# aaLogger.net
KiCad netlist of a schematic drawn in EAGLE
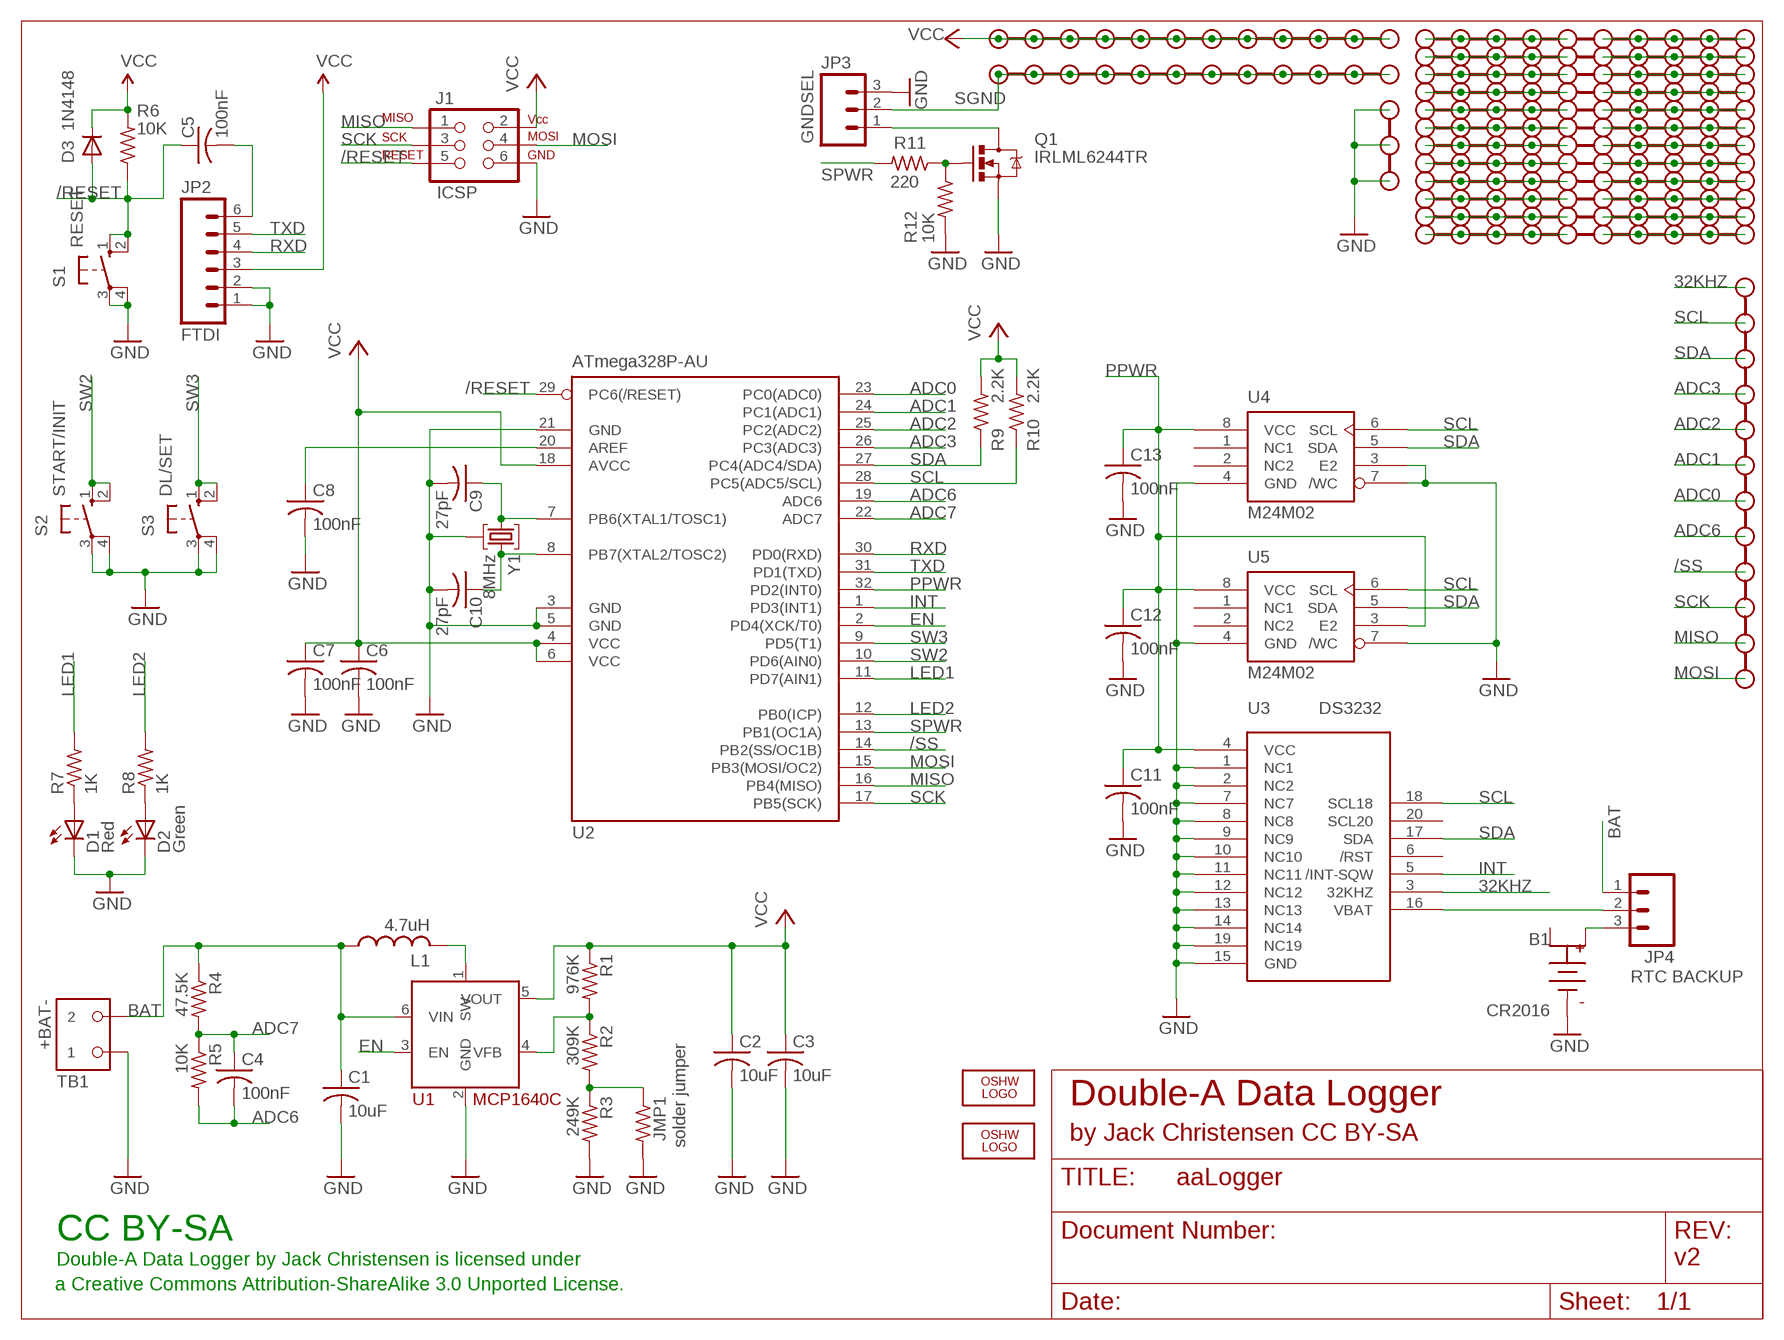
[diagram p0: schematic, sheet 1]

(export (version "E")
  (design (tool "Eeschema 10.0.6"))
  (components
    (comp (ref "B1")
      (value "CR2016")
      (footprint "eagle-import:BAT-HLD-002-SMT")
      (libsource (lib "eagle-import") (part "COIN-CELL-2016-SMT"))
    )
    (comp (ref "C1")
      (value "10uF")
      (footprint "eagle-import:M0805")
      (libsource (lib "eagle-import") (part "C-USM0805"))
    )
    (comp (ref "C2")
      (value "10uF")
      (footprint "eagle-import:M0805")
      (libsource (lib "eagle-import") (part "C-USM0805"))
    )
    (comp (ref "C3")
      (value "10uF")
      (footprint "eagle-import:M0805")
      (libsource (lib "eagle-import") (part "C-USM0805"))
    )
    (comp (ref "C4")
      (value "100nF")
      (footprint "eagle-import:M0805")
      (libsource (lib "eagle-import") (part "C-USM0805"))
    )
    (comp (ref "C5")
      (value "100nF")
      (footprint "eagle-import:M0805")
      (libsource (lib "eagle-import") (part "C-USM0805"))
    )
    (comp (ref "C6")
      (value "100nF")
      (footprint "eagle-import:M0805")
      (libsource (lib "eagle-import") (part "C-USM0805"))
    )
    (comp (ref "C7")
      (value "100nF")
      (footprint "eagle-import:M0805")
      (libsource (lib "eagle-import") (part "C-USM0805"))
    )
    (comp (ref "C8")
      (value "100nF")
      (footprint "eagle-import:M0805")
      (libsource (lib "eagle-import") (part "C-USM0805"))
    )
    (comp (ref "C9")
      (value "27pF")
      (footprint "eagle-import:M0805")
      (libsource (lib "eagle-import") (part "C-USM0805"))
    )
    (comp (ref "C10")
      (value "27pF")
      (footprint "eagle-import:M0805")
      (libsource (lib "eagle-import") (part "C-USM0805"))
    )
    (comp (ref "C11")
      (value "100nF")
      (footprint "eagle-import:M0805")
      (libsource (lib "eagle-import") (part "C-USM0805"))
    )
    (comp (ref "C12")
      (value "100nF")
      (footprint "eagle-import:M0805")
      (libsource (lib "eagle-import") (part "C-USM0805"))
    )
    (comp (ref "C13")
      (value "100nF")
      (footprint "eagle-import:M0805")
      (libsource (lib "eagle-import") (part "C-USM0805"))
    )
    (comp (ref "D1")
      (value "Red")
      (footprint "eagle-import:CHIPLED_1206")
      (libsource (lib "eagle-import") (part "LEDCHIPLED_1206"))
    )
    (comp (ref "D2")
      (value "Green")
      (footprint "eagle-import:CHIPLED_1206")
      (libsource (lib "eagle-import") (part "LEDCHIPLED_1206"))
    )
    (comp (ref "D3")
      (value "1N4148")
      (footprint "eagle-import:SOD-323F")
      (libsource (lib "eagle-import") (part "DIODESOD-323F"))
    )
    (comp (ref "J1")
      (value "ICSP")
      (footprint "eagle-import:2X3_LOCK")
      (libsource (lib "eagle-import") (part "AVR_SPI_PRG_62X3_LOCK"))
    )
    (comp (ref "JMP1")
      (value "solder jumper")
      (footprint "eagle-import:M0805")
      (libsource (lib "eagle-import") (part "R-US_M0805"))
    )
    (comp (ref "JP1")
      (value "PROTO-12NR")
      (footprint "eagle-import:PROTO-12-NR")
      (libsource (lib "eagle-import") (part "PROTO-12NR"))
    )
    (comp (ref "JP2")
      (value "FTDI")
      (footprint "eagle-import:1X06_LOCK")
      (libsource (lib "eagle-import") (part "M06LOCK"))
    )
    (comp (ref "JP3")
      (value "GNDSEL")
      (footprint "eagle-import:1X03_LOCK")
      (libsource (lib "eagle-import") (part "M03LOCK"))
    )
    (comp (ref "JP4")
      (value "RTC BACKUP")
      (footprint "eagle-import:1X03_LOCK")
      (libsource (lib "eagle-import") (part "M03LOCK"))
    )
    (comp (ref "L1")
      (value "4.7uH")
      (footprint "eagle-import:NRS5020")
      (libsource (lib "eagle-import") (part "INDUCTORNRS5020"))
    )
    (comp (ref "LOGO1")
      (value "OSHW_LOGO_8MILX0150-NT")
      (footprint "eagle-import:OSHW_8X150_NOTEXT")
      (libsource (lib "eagle-import") (part "OSHW_LOGO_8MILX0150-NT"))
    )
    (comp (ref "LOGO2")
      (value "OSHW_LOGO_8MILX0150-NT")
      (footprint "eagle-import:OSHW_8X150_NOTEXT")
      (libsource (lib "eagle-import") (part "OSHW_LOGO_8MILX0150-NT"))
    )
    (comp (ref "PR1")
      (value "PROTO-10")
      (footprint "eagle-import:PROTO-10")
      (libsource (lib "eagle-import") (part "PROTO-10"))
    )
    (comp (ref "PR2")
      (value "PROTO-10")
      (footprint "eagle-import:PROTO-10")
      (libsource (lib "eagle-import") (part "PROTO-10"))
    )
    (comp (ref "PR3")
      (value "PROTO-10")
      (footprint "eagle-import:PROTO-10")
      (libsource (lib "eagle-import") (part "PROTO-10"))
    )
    (comp (ref "PR4")
      (value "PROTO-10")
      (footprint "eagle-import:PROTO-10")
      (libsource (lib "eagle-import") (part "PROTO-10"))
    )
    (comp (ref "PR5")
      (value "PROTO-10")
      (footprint "eagle-import:PROTO-10")
      (libsource (lib "eagle-import") (part "PROTO-10"))
    )
    (comp (ref "PR6")
      (value "PROTO-10")
      (footprint "eagle-import:PROTO-10")
      (libsource (lib "eagle-import") (part "PROTO-10"))
    )
    (comp (ref "PR7")
      (value "PROTO-10")
      (footprint "eagle-import:PROTO-10")
      (libsource (lib "eagle-import") (part "PROTO-10"))
    )
    (comp (ref "PR8")
      (value "PROTO-10")
      (footprint "eagle-import:PROTO-10")
      (libsource (lib "eagle-import") (part "PROTO-10"))
    )
    (comp (ref "PR9")
      (value "PROTO-10")
      (footprint "eagle-import:PROTO-10")
      (libsource (lib "eagle-import") (part "PROTO-10"))
    )
    (comp (ref "PR10")
      (value "PROTO-10")
      (footprint "eagle-import:PROTO-10")
      (libsource (lib "eagle-import") (part "PROTO-10"))
    )
    (comp (ref "PR11")
      (value "PROTO-10")
      (footprint "eagle-import:PROTO-10")
      (libsource (lib "eagle-import") (part "PROTO-10"))
    )
    (comp (ref "PR12")
      (value "PROTO-10")
      (footprint "eagle-import:PROTO-10")
      (libsource (lib "eagle-import") (part "PROTO-10"))
    )
    (comp (ref "PR13")
      (value "PROTO-3")
      (footprint "eagle-import:PROTO-3")
      (libsource (lib "eagle-import") (part "PROTO-3"))
    )
    (comp (ref "Q1")
      (value "IRLML6244TR")
      (footprint "eagle-import:SOT23")
      (libsource (lib "eagle-import") (part "MOSFET-NCHANNELSOT23"))
    )
    (comp (ref "R1")
      (value "976K")
      (footprint "eagle-import:M0805")
      (libsource (lib "eagle-import") (part "R-US_M0805"))
    )
    (comp (ref "R2")
      (value "309K")
      (footprint "eagle-import:M0805")
      (libsource (lib "eagle-import") (part "R-US_M0805"))
    )
    (comp (ref "R3")
      (value "249K")
      (footprint "eagle-import:M0805")
      (libsource (lib "eagle-import") (part "R-US_M0805"))
    )
    (comp (ref "R4")
      (value "47.5K")
      (footprint "eagle-import:M0805")
      (libsource (lib "eagle-import") (part "R-US_M0805"))
    )
    (comp (ref "R5")
      (value "10K")
      (footprint "eagle-import:M0805")
      (libsource (lib "eagle-import") (part "R-US_M0805"))
    )
    (comp (ref "R6")
      (value "10K")
      (footprint "eagle-import:M0805")
      (libsource (lib "eagle-import") (part "R-US_M0805"))
    )
    (comp (ref "R7")
      (value "1K")
      (footprint "eagle-import:M0805")
      (libsource (lib "eagle-import") (part "R-US_M0805"))
    )
    (comp (ref "R8")
      (value "1K")
      (footprint "eagle-import:M0805")
      (libsource (lib "eagle-import") (part "R-US_M0805"))
    )
    (comp (ref "R9")
      (value "2.2K")
      (footprint "eagle-import:M0805")
      (libsource (lib "eagle-import") (part "R-US_M0805"))
    )
    (comp (ref "R10")
      (value "2.2K")
      (footprint "eagle-import:M0805")
      (libsource (lib "eagle-import") (part "R-US_M0805"))
    )
    (comp (ref "R11")
      (value "220")
      (footprint "eagle-import:M0805")
      (libsource (lib "eagle-import") (part "R-US_M0805"))
    )
    (comp (ref "R12")
      (value "10K")
      (footprint "eagle-import:M0805")
      (libsource (lib "eagle-import") (part "R-US_M0805"))
    )
    (comp (ref "S1")
      (value "RESET")
      (footprint "eagle-import:B3F-10XXOCT")
      (libsource (lib "eagle-import") (part "10-XXOCT"))
    )
    (comp (ref "S2")
      (value "START/INIT")
      (footprint "eagle-import:B3F-10XXOCT")
      (libsource (lib "eagle-import") (part "10-XXOCT"))
    )
    (comp (ref "S3")
      (value "DL/SET")
      (footprint "eagle-import:B3F-10XXOCT")
      (libsource (lib "eagle-import") (part "10-XXOCT"))
    )
    (comp (ref "TB1")
      (value "+BAT-")
      (footprint "eagle-import:OST-TB-2-3.5MM")
      (libsource (lib "eagle-import") (part "OST-TB-23.5MM"))
    )
    (comp (ref "U$1")
      (value "PROTO-12PROTO")
      (footprint "eagle-import:PROTO-12")
      (libsource (lib "eagle-import") (part "PROTO-12PROTO"))
    )
    (comp (ref "U$2")
      (value "PROTO-12PROTO")
      (footprint "eagle-import:PROTO-12")
      (libsource (lib "eagle-import") (part "PROTO-12PROTO"))
    )
    (comp (ref "U1")
      (value "MCP1640C")
      (footprint "eagle-import:SOT23-6")
      (libsource (lib "eagle-import") (part "MCP1640"))
    )
    (comp (ref "U2")
      (value "ATmega328P-AU")
      (footprint "eagle-import:TQFP32-08")
      (fields (field (name "MPN") "ATMEGA8-16AU"))
      (libsource (lib "eagle-import") (part "MEGA8-AI"))
    )
    (comp (ref "U3")
      (value "DS3232")
      (footprint "eagle-import:SO20W")
      (libsource (lib "eagle-import") (part "DS3232"))
    )
    (comp (ref "U4")
      (value "M24M02")
      (footprint "eagle-import:SO08")
      (libsource (lib "eagle-import") (part "M24M02"))
    )
    (comp (ref "U5")
      (value "M24M02")
      (footprint "eagle-import:SO08")
      (libsource (lib "eagle-import") (part "M24M02"))
    )
    (comp (ref "Y1")
      (value "8MHz")
      (footprint "eagle-import:RESONATOR")
      (libsource (lib "eagle-import") (part "RESONATOR"))
    )
  )
  (nets
    (net (code "1") (name "/32KHZ") (class "Default")
      (node (ref "JP1") (pin "1") (pinfunction "1_1") (pintype "bidirectional"))
      (node (ref "U3") (pin "3") (pinfunction "32KHZ_3") (pintype "bidirectional"))
    )
    (net (code "2") (name "/ADC0") (class "Default")
      (node (ref "JP1") (pin "7") (pinfunction "7_7") (pintype "bidirectional"))
      (node (ref "U2") (pin "23") (pinfunction "PC0(ADC0)_23") (pintype "bidirectional"))
    )
    (net (code "3") (name "/ADC1") (class "Default")
      (node (ref "JP1") (pin "6") (pinfunction "6_6") (pintype "bidirectional"))
      (node (ref "U2") (pin "24") (pinfunction "PC1(ADC1)_24") (pintype "bidirectional"))
    )
    (net (code "4") (name "/ADC2") (class "Default")
      (node (ref "JP1") (pin "5") (pinfunction "5_5") (pintype "bidirectional"))
      (node (ref "U2") (pin "25") (pinfunction "PC2(ADC2)_25") (pintype "bidirectional"))
    )
    (net (code "5") (name "/ADC3") (class "Default")
      (node (ref "JP1") (pin "4") (pinfunction "4_4") (pintype "bidirectional"))
      (node (ref "U2") (pin "26") (pinfunction "PC3(ADC3)_26") (pintype "bidirectional"))
    )
    (net (code "6") (name "/ADC6") (class "Default")
      (node (ref "C4") (pin "2") (pinfunction "2_2") (pintype "passive"))
      (node (ref "JP1") (pin "8") (pinfunction "8_8") (pintype "bidirectional"))
      (node (ref "R5") (pin "2") (pinfunction "2_2") (pintype "passive"))
      (node (ref "U2") (pin "19") (pinfunction "ADC6_19") (pintype "bidirectional"))
    )
    (net (code "7") (name "/ADC7") (class "Default")
      (node (ref "C4") (pin "1") (pinfunction "1_1") (pintype "passive"))
      (node (ref "R4") (pin "2") (pinfunction "2_2") (pintype "passive"))
      (node (ref "R5") (pin "1") (pinfunction "1_1") (pintype "passive"))
      (node (ref "U2") (pin "22") (pinfunction "ADC7_22") (pintype "bidirectional"))
    )
    (net (code "8") (name "/BAT") (class "Default")
      (node (ref "C1") (pin "1") (pinfunction "1_1") (pintype "passive"))
      (node (ref "JP4") (pin "1") (pinfunction "1_1") (pintype "passive"))
      (node (ref "L1") (pin "P$1") (pinfunction "1_P$1") (pintype "passive"))
      (node (ref "R4") (pin "1") (pinfunction "1_1") (pintype "passive"))
      (node (ref "TB1") (pin "P$2") (pinfunction "2_P$2") (pintype "passive"))
      (node (ref "U1") (pin "6") (pinfunction "VIN_6") (pintype "passive"))
    )
    (net (code "9") (name "/EN") (class "Default")
      (node (ref "U1") (pin "3") (pinfunction "EN_3") (pintype "passive"))
      (node (ref "U2") (pin "2") (pinfunction "PD4(XCK/T0)_2") (pintype "bidirectional"))
    )
    (net (code "10") (name "/INT") (class "Default")
      (node (ref "U2") (pin "1") (pinfunction "PD3(INT1)_1") (pintype "bidirectional"))
      (node (ref "U3") (pin "5") (pinfunction "/INT-SQW_5") (pintype "bidirectional"))
    )
    (net (code "11") (name "/LED1") (class "Default")
      (node (ref "R7") (pin "2") (pinfunction "2_2") (pintype "passive"))
      (node (ref "U2") (pin "11") (pinfunction "PD7(AIN1)_11") (pintype "bidirectional"))
    )
    (net (code "12") (name "/LED2") (class "Default")
      (node (ref "R8") (pin "2") (pinfunction "2_2") (pintype "passive"))
      (node (ref "U2") (pin "12") (pinfunction "PB0(ICP)_12") (pintype "bidirectional"))
    )
    (net (code "13") (name "/MISO") (class "Default")
      (node (ref "J1") (pin "1") (pinfunction "1_1") (pintype "passive"))
      (node (ref "JP1") (pin "11") (pinfunction "11_11") (pintype "bidirectional"))
      (node (ref "U2") (pin "16") (pinfunction "PB4(MISO)_16") (pintype "bidirectional"))
    )
    (net (code "14") (name "/MOSI") (class "Default")
      (node (ref "J1") (pin "4") (pinfunction "4_4") (pintype "passive"))
      (node (ref "JP1") (pin "12") (pinfunction "12_12") (pintype "bidirectional"))
      (node (ref "U2") (pin "15") (pinfunction "PB3(MOSI/OC2)_15") (pintype "bidirectional"))
    )
    (net (code "15") (name "/PPWR") (class "Default")
      (node (ref "C11") (pin "1") (pinfunction "1_1") (pintype "passive"))
      (node (ref "C12") (pin "1") (pinfunction "1_1") (pintype "passive"))
      (node (ref "C13") (pin "1") (pinfunction "1_1") (pintype "passive"))
      (node (ref "U2") (pin "32") (pinfunction "PD2(INT0)_32") (pintype "bidirectional"))
      (node (ref "U3") (pin "4") (pinfunction "VCC_4") (pintype "bidirectional"))
      (node (ref "U4") (pin "8") (pinfunction "VCC_8") (pintype "bidirectional"))
      (node (ref "U5") (pin "3") (pinfunction "E2_3") (pintype "bidirectional"))
      (node (ref "U5") (pin "8") (pinfunction "VCC_8") (pintype "bidirectional"))
    )
    (net (code "16") (name "/RXD") (class "Default")
      (node (ref "JP2") (pin "4") (pinfunction "4_4") (pintype "passive"))
      (node (ref "U2") (pin "30") (pinfunction "PD0(RXD)_30") (pintype "bidirectional"))
    )
    (net (code "17") (name "/SCK") (class "Default")
      (node (ref "J1") (pin "3") (pinfunction "3_3") (pintype "passive"))
      (node (ref "JP1") (pin "10") (pinfunction "10_10") (pintype "bidirectional"))
      (node (ref "U2") (pin "17") (pinfunction "PB5(SCK)_17") (pintype "bidirectional"))
    )
    (net (code "18") (name "/SCL") (class "Default")
      (node (ref "JP1") (pin "2") (pinfunction "2_2") (pintype "bidirectional"))
      (node (ref "R10") (pin "1") (pinfunction "1_1") (pintype "passive"))
      (node (ref "U2") (pin "28") (pinfunction "PC5(ADC5/SCL)_28") (pintype "bidirectional"))
      (node (ref "U3") (pin "18") (pinfunction "SCL18_18") (pintype "bidirectional"))
      (node (ref "U4") (pin "6") (pinfunction "SCL_6") (pintype "bidirectional"))
      (node (ref "U5") (pin "6") (pinfunction "SCL_6") (pintype "bidirectional"))
    )
    (net (code "19") (name "/SDA") (class "Default")
      (node (ref "JP1") (pin "3") (pinfunction "3_3") (pintype "bidirectional"))
      (node (ref "R9") (pin "1") (pinfunction "1_1") (pintype "passive"))
      (node (ref "U2") (pin "27") (pinfunction "PC4(ADC4/SDA)_27") (pintype "bidirectional"))
      (node (ref "U3") (pin "17") (pinfunction "SDA_17") (pintype "bidirectional"))
      (node (ref "U4") (pin "5") (pinfunction "SDA_5") (pintype "bidirectional"))
      (node (ref "U5") (pin "5") (pinfunction "SDA_5") (pintype "bidirectional"))
    )
    (net (code "20") (name "/SGND") (class "Default")
      (node (ref "JP3") (pin "2") (pinfunction "2_2") (pintype "passive"))
      (node (ref "U$2") (pin "1") (pinfunction "1_1") (pintype "bidirectional"))
      (node (ref "U$2") (pin "10") (pinfunction "10_10") (pintype "bidirectional"))
      (node (ref "U$2") (pin "11") (pinfunction "11_11") (pintype "bidirectional"))
      (node (ref "U$2") (pin "12") (pinfunction "12_12") (pintype "bidirectional"))
      (node (ref "U$2") (pin "2") (pinfunction "2_2") (pintype "bidirectional"))
      (node (ref "U$2") (pin "3") (pinfunction "3_3") (pintype "bidirectional"))
      (node (ref "U$2") (pin "4") (pinfunction "4_4") (pintype "bidirectional"))
      (node (ref "U$2") (pin "5") (pinfunction "5_5") (pintype "bidirectional"))
      (node (ref "U$2") (pin "6") (pinfunction "6_6") (pintype "bidirectional"))
      (node (ref "U$2") (pin "7") (pinfunction "7_7") (pintype "bidirectional"))
      (node (ref "U$2") (pin "8") (pinfunction "8_8") (pintype "bidirectional"))
      (node (ref "U$2") (pin "9") (pinfunction "9_9") (pintype "bidirectional"))
    )
    (net (code "21") (name "/SPWR") (class "Default")
      (node (ref "R11") (pin "2") (pinfunction "2_2") (pintype "passive"))
      (node (ref "U2") (pin "13") (pinfunction "PB1(OC1A)_13") (pintype "bidirectional"))
    )
    (net (code "22") (name "/SW2") (class "Default")
      (node (ref "S2") (pin "1") (pinfunction "S_1") (pintype "passive"))
      (node (ref "S2") (pin "2") (pinfunction "S1_2") (pintype "passive"))
      (node (ref "U2") (pin "10") (pinfunction "PD6(AIN0)_10") (pintype "bidirectional"))
    )
    (net (code "23") (name "/SW3") (class "Default")
      (node (ref "S3") (pin "1") (pinfunction "S_1") (pintype "passive"))
      (node (ref "S3") (pin "2") (pinfunction "S1_2") (pintype "passive"))
      (node (ref "U2") (pin "9") (pinfunction "PD5(T1)_9") (pintype "bidirectional"))
    )
    (net (code "24") (name "/TXD") (class "Default")
      (node (ref "JP2") (pin "5") (pinfunction "5_5") (pintype "passive"))
      (node (ref "U2") (pin "31") (pinfunction "PD1(TXD)_31") (pintype "bidirectional"))
    )
    (net (code "25") (name "/{slash}RESET") (class "Default")
      (node (ref "C5") (pin "1") (pinfunction "1_1") (pintype "passive"))
      (node (ref "D3") (pin "A") (pinfunction "A_A") (pintype "passive"))
      (node (ref "J1") (pin "5") (pinfunction "5_5") (pintype "passive"))
      (node (ref "R6") (pin "1") (pinfunction "1_1") (pintype "passive"))
      (node (ref "S1") (pin "1") (pinfunction "S_1") (pintype "passive"))
      (node (ref "S1") (pin "2") (pinfunction "S1_2") (pintype "passive"))
      (node (ref "U2") (pin "29") (pinfunction "PC6(/RESET)_29") (pintype "bidirectional"))
    )
    (net (code "26") (name "/{slash}SS") (class "Default")
      (node (ref "JP1") (pin "9") (pinfunction "9_9") (pintype "bidirectional"))
      (node (ref "U2") (pin "14") (pinfunction "PB2(SS/OC1B)_14") (pintype "bidirectional"))
    )
    (net (code "27") (name "GND") (class "Default")
      (node (ref "B1") (pin "NEG") (pinfunction "B-_NEG") (pintype "passive"))
      (node (ref "C1") (pin "2") (pinfunction "2_2") (pintype "passive"))
      (node (ref "C10") (pin "2") (pinfunction "2_2") (pintype "passive"))
      (node (ref "C11") (pin "2") (pinfunction "2_2") (pintype "passive"))
      (node (ref "C12") (pin "2") (pinfunction "2_2") (pintype "passive"))
      (node (ref "C13") (pin "2") (pinfunction "2_2") (pintype "passive"))
      (node (ref "C2") (pin "2") (pinfunction "2_2") (pintype "passive"))
      (node (ref "C3") (pin "2") (pinfunction "2_2") (pintype "passive"))
      (node (ref "C6") (pin "2") (pinfunction "2_2") (pintype "passive"))
      (node (ref "C7") (pin "2") (pinfunction "2_2") (pintype "passive"))
      (node (ref "C8") (pin "2") (pinfunction "2_2") (pintype "passive"))
      (node (ref "C9") (pin "2") (pinfunction "2_2") (pintype "passive"))
      (node (ref "D1") (pin "C") (pinfunction "C_C") (pintype "passive"))
      (node (ref "D2") (pin "C") (pinfunction "C_C") (pintype "passive"))
      (node (ref "J1") (pin "6") (pinfunction "6_6") (pintype "passive"))
      (node (ref "JMP1") (pin "2") (pinfunction "2_2") (pintype "passive"))
      (node (ref "JP2") (pin "1") (pinfunction "1_1") (pintype "passive"))
      (node (ref "JP2") (pin "2") (pinfunction "2_2") (pintype "passive"))
      (node (ref "JP3") (pin "3") (pinfunction "3_3") (pintype "passive"))
      (node (ref "PR13") (pin "1") (pinfunction "1_1") (pintype "bidirectional"))
      (node (ref "PR13") (pin "2") (pinfunction "2_2") (pintype "bidirectional"))
      (node (ref "PR13") (pin "3") (pinfunction "3_3") (pintype "bidirectional"))
      (node (ref "Q1") (pin "2") (pinfunction "S_2") (pintype "passive"))
      (node (ref "R12") (pin "2") (pinfunction "2_2") (pintype "passive"))
      (node (ref "R3") (pin "2") (pinfunction "2_2") (pintype "passive"))
      (node (ref "S1") (pin "3") (pinfunction "P_3") (pintype "passive"))
      (node (ref "S1") (pin "4") (pinfunction "P1_4") (pintype "passive"))
      (node (ref "S2") (pin "3") (pinfunction "P_3") (pintype "passive"))
      (node (ref "S2") (pin "4") (pinfunction "P1_4") (pintype "passive"))
      (node (ref "S3") (pin "3") (pinfunction "P_3") (pintype "passive"))
      (node (ref "S3") (pin "4") (pinfunction "P1_4") (pintype "passive"))
      (node (ref "TB1") (pin "P$1") (pinfunction "1_P$1") (pintype "passive"))
      (node (ref "U1") (pin "2") (pinfunction "GND_2") (pintype "passive"))
      (node (ref "U2") (pin "21") (pinfunction "GND_21") (pintype "power_in"))
      (node (ref "U2") (pin "3") (pinfunction "GND_3") (pintype "power_in"))
      (node (ref "U2") (pin "5") (pinfunction "GND_5") (pintype "power_in"))
      (node (ref "U3") (pin "1") (pinfunction "NC1_1") (pintype "bidirectional"))
      (node (ref "U3") (pin "10") (pinfunction "NC10_10") (pintype "bidirectional"))
      (node (ref "U3") (pin "11") (pinfunction "NC11_11") (pintype "bidirectional"))
      (node (ref "U3") (pin "12") (pinfunction "NC12_12") (pintype "bidirectional"))
      (node (ref "U3") (pin "13") (pinfunction "NC13_13") (pintype "bidirectional"))
      (node (ref "U3") (pin "14") (pinfunction "NC14_14") (pintype "bidirectional"))
      (node (ref "U3") (pin "15") (pinfunction "GND_15") (pintype "bidirectional"))
      (node (ref "U3") (pin "19") (pinfunction "NC19_19") (pintype "bidirectional"))
      (node (ref "U3") (pin "2") (pinfunction "NC2_2") (pintype "bidirectional"))
      (node (ref "U3") (pin "7") (pinfunction "NC7_7") (pintype "bidirectional"))
      (node (ref "U3") (pin "8") (pinfunction "NC8_8") (pintype "bidirectional"))
      (node (ref "U3") (pin "9") (pinfunction "NC9_9") (pintype "bidirectional"))
      (node (ref "U4") (pin "3") (pinfunction "E2_3") (pintype "bidirectional"))
      (node (ref "U4") (pin "4") (pinfunction "GND_4") (pintype "bidirectional"))
      (node (ref "U4") (pin "7") (pinfunction "/WC_7") (pintype "bidirectional"))
      (node (ref "U5") (pin "4") (pinfunction "GND_4") (pintype "bidirectional"))
      (node (ref "U5") (pin "7") (pinfunction "/WC_7") (pintype "bidirectional"))
      (node (ref "Y1") (pin "2") (pinfunction "2_2") (pintype "passive"))
    )
    (net (code "28") (name "Net-(B1-PadPOS1)") (class "Default")
      (node (ref "B1") (pin "POS1") (pinfunction "POS1_POS1") (pintype "passive"))
      (node (ref "JP4") (pin "3") (pinfunction "3_3") (pintype "passive"))
    )
    (net (code "29") (name "Net-(C5-Pad2)") (class "Default")
      (node (ref "C5") (pin "2") (pinfunction "2_2") (pintype "passive"))
      (node (ref "JP2") (pin "6") (pinfunction "6_6") (pintype "passive"))
    )
    (net (code "30") (name "Net-(D1-PadA)") (class "Default")
      (node (ref "D1") (pin "A") (pinfunction "A_A") (pintype "passive"))
      (node (ref "R7") (pin "1") (pinfunction "1_1") (pintype "passive"))
    )
    (net (code "31") (name "Net-(D2-PadA)") (class "Default")
      (node (ref "D2") (pin "A") (pinfunction "A_A") (pintype "passive"))
      (node (ref "R8") (pin "1") (pinfunction "1_1") (pintype "passive"))
    )
    (net (code "32") (name "Net-(JMP1-Pad1)") (class "Default")
      (node (ref "JMP1") (pin "1") (pinfunction "1_1") (pintype "passive"))
      (node (ref "R2") (pin "2") (pinfunction "2_2") (pintype "passive"))
      (node (ref "R3") (pin "1") (pinfunction "1_1") (pintype "passive"))
    )
    (net (code "33") (name "Net-(L1-2)") (class "Default")
      (node (ref "L1") (pin "P$2") (pinfunction "2_P$2") (pintype "passive"))
      (node (ref "U1") (pin "1") (pinfunction "SW_1") (pintype "passive"))
    )
    (net (code "34") (name "Net-(PR1-Pad1)") (class "Default")
      (node (ref "PR1") (pin "1") (pinfunction "1_1") (pintype "bidirectional"))
      (node (ref "PR1") (pin "2") (pinfunction "2_2") (pintype "bidirectional"))
      (node (ref "PR1") (pin "3") (pinfunction "3_3") (pintype "bidirectional"))
      (node (ref "PR1") (pin "4") (pinfunction "4_4") (pintype "bidirectional"))
      (node (ref "PR1") (pin "5") (pinfunction "5_5") (pintype "bidirectional"))
    )
    (net (code "35") (name "Net-(PR1-Pad10)") (class "Default")
      (node (ref "PR1") (pin "10") (pinfunction "10_10") (pintype "bidirectional"))
      (node (ref "PR1") (pin "6") (pinfunction "6_6") (pintype "bidirectional"))
      (node (ref "PR1") (pin "7") (pinfunction "7_7") (pintype "bidirectional"))
      (node (ref "PR1") (pin "8") (pinfunction "8_8") (pintype "bidirectional"))
      (node (ref "PR1") (pin "9") (pinfunction "9_9") (pintype "bidirectional"))
    )
    (net (code "36") (name "Net-(PR2-Pad1)") (class "Default")
      (node (ref "PR2") (pin "1") (pinfunction "1_1") (pintype "bidirectional"))
      (node (ref "PR2") (pin "2") (pinfunction "2_2") (pintype "bidirectional"))
      (node (ref "PR2") (pin "3") (pinfunction "3_3") (pintype "bidirectional"))
      (node (ref "PR2") (pin "4") (pinfunction "4_4") (pintype "bidirectional"))
      (node (ref "PR2") (pin "5") (pinfunction "5_5") (pintype "bidirectional"))
    )
    (net (code "37") (name "Net-(PR2-Pad10)") (class "Default")
      (node (ref "PR2") (pin "10") (pinfunction "10_10") (pintype "bidirectional"))
      (node (ref "PR2") (pin "6") (pinfunction "6_6") (pintype "bidirectional"))
      (node (ref "PR2") (pin "7") (pinfunction "7_7") (pintype "bidirectional"))
      (node (ref "PR2") (pin "8") (pinfunction "8_8") (pintype "bidirectional"))
      (node (ref "PR2") (pin "9") (pinfunction "9_9") (pintype "bidirectional"))
    )
    (net (code "38") (name "Net-(PR3-Pad1)") (class "Default")
      (node (ref "PR3") (pin "1") (pinfunction "1_1") (pintype "bidirectional"))
      (node (ref "PR3") (pin "2") (pinfunction "2_2") (pintype "bidirectional"))
      (node (ref "PR3") (pin "3") (pinfunction "3_3") (pintype "bidirectional"))
      (node (ref "PR3") (pin "4") (pinfunction "4_4") (pintype "bidirectional"))
      (node (ref "PR3") (pin "5") (pinfunction "5_5") (pintype "bidirectional"))
    )
    (net (code "39") (name "Net-(PR3-Pad10)") (class "Default")
      (node (ref "PR3") (pin "10") (pinfunction "10_10") (pintype "bidirectional"))
      (node (ref "PR3") (pin "6") (pinfunction "6_6") (pintype "bidirectional"))
      (node (ref "PR3") (pin "7") (pinfunction "7_7") (pintype "bidirectional"))
      (node (ref "PR3") (pin "8") (pinfunction "8_8") (pintype "bidirectional"))
      (node (ref "PR3") (pin "9") (pinfunction "9_9") (pintype "bidirectional"))
    )
    (net (code "40") (name "Net-(PR4-Pad1)") (class "Default")
      (node (ref "PR4") (pin "1") (pinfunction "1_1") (pintype "bidirectional"))
      (node (ref "PR4") (pin "2") (pinfunction "2_2") (pintype "bidirectional"))
      (node (ref "PR4") (pin "3") (pinfunction "3_3") (pintype "bidirectional"))
      (node (ref "PR4") (pin "4") (pinfunction "4_4") (pintype "bidirectional"))
      (node (ref "PR4") (pin "5") (pinfunction "5_5") (pintype "bidirectional"))
    )
    (net (code "41") (name "Net-(PR4-Pad10)") (class "Default")
      (node (ref "PR4") (pin "10") (pinfunction "10_10") (pintype "bidirectional"))
      (node (ref "PR4") (pin "6") (pinfunction "6_6") (pintype "bidirectional"))
      (node (ref "PR4") (pin "7") (pinfunction "7_7") (pintype "bidirectional"))
      (node (ref "PR4") (pin "8") (pinfunction "8_8") (pintype "bidirectional"))
      (node (ref "PR4") (pin "9") (pinfunction "9_9") (pintype "bidirectional"))
    )
    (net (code "42") (name "Net-(PR5-Pad1)") (class "Default")
      (node (ref "PR5") (pin "1") (pinfunction "1_1") (pintype "bidirectional"))
      (node (ref "PR5") (pin "2") (pinfunction "2_2") (pintype "bidirectional"))
      (node (ref "PR5") (pin "3") (pinfunction "3_3") (pintype "bidirectional"))
      (node (ref "PR5") (pin "4") (pinfunction "4_4") (pintype "bidirectional"))
      (node (ref "PR5") (pin "5") (pinfunction "5_5") (pintype "bidirectional"))
    )
    (net (code "43") (name "Net-(PR5-Pad10)") (class "Default")
      (node (ref "PR5") (pin "10") (pinfunction "10_10") (pintype "bidirectional"))
      (node (ref "PR5") (pin "6") (pinfunction "6_6") (pintype "bidirectional"))
      (node (ref "PR5") (pin "7") (pinfunction "7_7") (pintype "bidirectional"))
      (node (ref "PR5") (pin "8") (pinfunction "8_8") (pintype "bidirectional"))
      (node (ref "PR5") (pin "9") (pinfunction "9_9") (pintype "bidirectional"))
    )
    (net (code "44") (name "Net-(PR6-Pad1)") (class "Default")
      (node (ref "PR6") (pin "1") (pinfunction "1_1") (pintype "bidirectional"))
      (node (ref "PR6") (pin "2") (pinfunction "2_2") (pintype "bidirectional"))
      (node (ref "PR6") (pin "3") (pinfunction "3_3") (pintype "bidirectional"))
      (node (ref "PR6") (pin "4") (pinfunction "4_4") (pintype "bidirectional"))
      (node (ref "PR6") (pin "5") (pinfunction "5_5") (pintype "bidirectional"))
    )
    (net (code "45") (name "Net-(PR6-Pad10)") (class "Default")
      (node (ref "PR6") (pin "10") (pinfunction "10_10") (pintype "bidirectional"))
      (node (ref "PR6") (pin "6") (pinfunction "6_6") (pintype "bidirectional"))
      (node (ref "PR6") (pin "7") (pinfunction "7_7") (pintype "bidirectional"))
      (node (ref "PR6") (pin "8") (pinfunction "8_8") (pintype "bidirectional"))
      (node (ref "PR6") (pin "9") (pinfunction "9_9") (pintype "bidirectional"))
    )
    (net (code "46") (name "Net-(PR7-Pad1)") (class "Default")
      (node (ref "PR7") (pin "1") (pinfunction "1_1") (pintype "bidirectional"))
      (node (ref "PR7") (pin "2") (pinfunction "2_2") (pintype "bidirectional"))
      (node (ref "PR7") (pin "3") (pinfunction "3_3") (pintype "bidirectional"))
      (node (ref "PR7") (pin "4") (pinfunction "4_4") (pintype "bidirectional"))
      (node (ref "PR7") (pin "5") (pinfunction "5_5") (pintype "bidirectional"))
    )
    (net (code "47") (name "Net-(PR7-Pad10)") (class "Default")
      (node (ref "PR7") (pin "10") (pinfunction "10_10") (pintype "bidirectional"))
      (node (ref "PR7") (pin "6") (pinfunction "6_6") (pintype "bidirectional"))
      (node (ref "PR7") (pin "7") (pinfunction "7_7") (pintype "bidirectional"))
      (node (ref "PR7") (pin "8") (pinfunction "8_8") (pintype "bidirectional"))
      (node (ref "PR7") (pin "9") (pinfunction "9_9") (pintype "bidirectional"))
    )
    (net (code "48") (name "Net-(PR8-Pad1)") (class "Default")
      (node (ref "PR8") (pin "1") (pinfunction "1_1") (pintype "bidirectional"))
      (node (ref "PR8") (pin "2") (pinfunction "2_2") (pintype "bidirectional"))
      (node (ref "PR8") (pin "3") (pinfunction "3_3") (pintype "bidirectional"))
      (node (ref "PR8") (pin "4") (pinfunction "4_4") (pintype "bidirectional"))
      (node (ref "PR8") (pin "5") (pinfunction "5_5") (pintype "bidirectional"))
    )
    (net (code "49") (name "Net-(PR8-Pad10)") (class "Default")
      (node (ref "PR8") (pin "10") (pinfunction "10_10") (pintype "bidirectional"))
      (node (ref "PR8") (pin "6") (pinfunction "6_6") (pintype "bidirectional"))
      (node (ref "PR8") (pin "7") (pinfunction "7_7") (pintype "bidirectional"))
      (node (ref "PR8") (pin "8") (pinfunction "8_8") (pintype "bidirectional"))
      (node (ref "PR8") (pin "9") (pinfunction "9_9") (pintype "bidirectional"))
    )
    (net (code "50") (name "Net-(PR9-Pad1)") (class "Default")
      (node (ref "PR9") (pin "1") (pinfunction "1_1") (pintype "bidirectional"))
      (node (ref "PR9") (pin "2") (pinfunction "2_2") (pintype "bidirectional"))
      (node (ref "PR9") (pin "3") (pinfunction "3_3") (pintype "bidirectional"))
      (node (ref "PR9") (pin "4") (pinfunction "4_4") (pintype "bidirectional"))
      (node (ref "PR9") (pin "5") (pinfunction "5_5") (pintype "bidirectional"))
    )
    (net (code "51") (name "Net-(PR9-Pad10)") (class "Default")
      (node (ref "PR9") (pin "10") (pinfunction "10_10") (pintype "bidirectional"))
      (node (ref "PR9") (pin "6") (pinfunction "6_6") (pintype "bidirectional"))
      (node (ref "PR9") (pin "7") (pinfunction "7_7") (pintype "bidirectional"))
      (node (ref "PR9") (pin "8") (pinfunction "8_8") (pintype "bidirectional"))
      (node (ref "PR9") (pin "9") (pinfunction "9_9") (pintype "bidirectional"))
    )
    (net (code "52") (name "Net-(PR10-Pad1)") (class "Default")
      (node (ref "PR10") (pin "1") (pinfunction "1_1") (pintype "bidirectional"))
      (node (ref "PR10") (pin "2") (pinfunction "2_2") (pintype "bidirectional"))
      (node (ref "PR10") (pin "3") (pinfunction "3_3") (pintype "bidirectional"))
      (node (ref "PR10") (pin "4") (pinfunction "4_4") (pintype "bidirectional"))
      (node (ref "PR10") (pin "5") (pinfunction "5_5") (pintype "bidirectional"))
    )
    (net (code "53") (name "Net-(PR10-Pad10)") (class "Default")
      (node (ref "PR10") (pin "10") (pinfunction "10_10") (pintype "bidirectional"))
      (node (ref "PR10") (pin "6") (pinfunction "6_6") (pintype "bidirectional"))
      (node (ref "PR10") (pin "7") (pinfunction "7_7") (pintype "bidirectional"))
      (node (ref "PR10") (pin "8") (pinfunction "8_8") (pintype "bidirectional"))
      (node (ref "PR10") (pin "9") (pinfunction "9_9") (pintype "bidirectional"))
    )
    (net (code "54") (name "Net-(PR11-Pad1)") (class "Default")
      (node (ref "PR11") (pin "1") (pinfunction "1_1") (pintype "bidirectional"))
      (node (ref "PR11") (pin "2") (pinfunction "2_2") (pintype "bidirectional"))
      (node (ref "PR11") (pin "3") (pinfunction "3_3") (pintype "bidirectional"))
      (node (ref "PR11") (pin "4") (pinfunction "4_4") (pintype "bidirectional"))
      (node (ref "PR11") (pin "5") (pinfunction "5_5") (pintype "bidirectional"))
    )
    (net (code "55") (name "Net-(PR11-Pad10)") (class "Default")
      (node (ref "PR11") (pin "10") (pinfunction "10_10") (pintype "bidirectional"))
      (node (ref "PR11") (pin "6") (pinfunction "6_6") (pintype "bidirectional"))
      (node (ref "PR11") (pin "7") (pinfunction "7_7") (pintype "bidirectional"))
      (node (ref "PR11") (pin "8") (pinfunction "8_8") (pintype "bidirectional"))
      (node (ref "PR11") (pin "9") (pinfunction "9_9") (pintype "bidirectional"))
    )
    (net (code "56") (name "Net-(PR12-Pad1)") (class "Default")
      (node (ref "PR12") (pin "1") (pinfunction "1_1") (pintype "bidirectional"))
      (node (ref "PR12") (pin "2") (pinfunction "2_2") (pintype "bidirectional"))
      (node (ref "PR12") (pin "3") (pinfunction "3_3") (pintype "bidirectional"))
      (node (ref "PR12") (pin "4") (pinfunction "4_4") (pintype "bidirectional"))
      (node (ref "PR12") (pin "5") (pinfunction "5_5") (pintype "bidirectional"))
    )
    (net (code "57") (name "Net-(PR12-Pad10)") (class "Default")
      (node (ref "PR12") (pin "10") (pinfunction "10_10") (pintype "bidirectional"))
      (node (ref "PR12") (pin "6") (pinfunction "6_6") (pintype "bidirectional"))
      (node (ref "PR12") (pin "7") (pinfunction "7_7") (pintype "bidirectional"))
      (node (ref "PR12") (pin "8") (pinfunction "8_8") (pintype "bidirectional"))
      (node (ref "PR12") (pin "9") (pinfunction "9_9") (pintype "bidirectional"))
    )
    (net (code "58") (name "Net-(Q1-D)") (class "Default")
      (node (ref "JP3") (pin "1") (pinfunction "1_1") (pintype "passive"))
      (node (ref "Q1") (pin "3") (pinfunction "D_3") (pintype "passive"))
    )
    (net (code "59") (name "Net-(Q1-G)") (class "Default")
      (node (ref "Q1") (pin "1") (pinfunction "G_1") (pintype "passive"))
      (node (ref "R11") (pin "1") (pinfunction "1_1") (pintype "passive"))
      (node (ref "R12") (pin "1") (pinfunction "1_1") (pintype "passive"))
    )
    (net (code "60") (name "Net-(U1-VFB)") (class "Default")
      (node (ref "R1") (pin "2") (pinfunction "2_2") (pintype "passive"))
      (node (ref "R2") (pin "1") (pinfunction "1_1") (pintype "passive"))
      (node (ref "U1") (pin "4") (pinfunction "VFB_4") (pintype "passive"))
    )
    (net (code "61") (name "Net-(U2-AREF)") (class "Default")
      (node (ref "C8") (pin "1") (pinfunction "1_1") (pintype "passive"))
      (node (ref "U2") (pin "20") (pinfunction "AREF_20") (pintype "passive"))
    )
    (net (code "62") (name "Net-(U2-PB6(XTAL1{slash}TOSC1))") (class "Default")
      (node (ref "C9") (pin "1") (pinfunction "1_1") (pintype "passive"))
      (node (ref "U2") (pin "7") (pinfunction "PB6(XTAL1/TOSC1)_7") (pintype "bidirectional"))
      (node (ref "Y1") (pin "1") (pinfunction "1_1") (pintype "passive"))
    )
    (net (code "63") (name "Net-(U2-PB7(XTAL2{slash}TOSC2))") (class "Default")
      (node (ref "C10") (pin "1") (pinfunction "1_1") (pintype "passive"))
      (node (ref "U2") (pin "8") (pinfunction "PB7(XTAL2/TOSC2)_8") (pintype "bidirectional"))
      (node (ref "Y1") (pin "3") (pinfunction "3_3") (pintype "passive"))
    )
    (net (code "64") (name "Net-(U3-VBAT)") (class "Default")
      (node (ref "JP4") (pin "2") (pinfunction "2_2") (pintype "passive"))
      (node (ref "U3") (pin "16") (pinfunction "VBAT_16") (pintype "bidirectional"))
    )
    (net (code "65") (name "VCC") (class "Default")
      (node (ref "C2") (pin "1") (pinfunction "1_1") (pintype "passive"))
      (node (ref "C3") (pin "1") (pinfunction "1_1") (pintype "passive"))
      (node (ref "C6") (pin "1") (pinfunction "1_1") (pintype "passive"))
      (node (ref "C7") (pin "1") (pinfunction "1_1") (pintype "passive"))
      (node (ref "D3") (pin "K") (pinfunction "K_K") (pintype "passive"))
      (node (ref "J1") (pin "2") (pinfunction "2_2") (pintype "passive"))
      (node (ref "JP2") (pin "3") (pinfunction "3_3") (pintype "passive"))
      (node (ref "R1") (pin "1") (pinfunction "1_1") (pintype "passive"))
      (node (ref "R10") (pin "2") (pinfunction "2_2") (pintype "passive"))
      (node (ref "R6") (pin "2") (pinfunction "2_2") (pintype "passive"))
      (node (ref "R9") (pin "2") (pinfunction "2_2") (pintype "passive"))
      (node (ref "U$1") (pin "1") (pinfunction "1_1") (pintype "bidirectional"))
      (node (ref "U$1") (pin "10") (pinfunction "10_10") (pintype "bidirectional"))
      (node (ref "U$1") (pin "11") (pinfunction "11_11") (pintype "bidirectional"))
      (node (ref "U$1") (pin "12") (pinfunction "12_12") (pintype "bidirectional"))
      (node (ref "U$1") (pin "2") (pinfunction "2_2") (pintype "bidirectional"))
      (node (ref "U$1") (pin "3") (pinfunction "3_3") (pintype "bidirectional"))
      (node (ref "U$1") (pin "4") (pinfunction "4_4") (pintype "bidirectional"))
      (node (ref "U$1") (pin "5") (pinfunction "5_5") (pintype "bidirectional"))
      (node (ref "U$1") (pin "6") (pinfunction "6_6") (pintype "bidirectional"))
      (node (ref "U$1") (pin "7") (pinfunction "7_7") (pintype "bidirectional"))
      (node (ref "U$1") (pin "8") (pinfunction "8_8") (pintype "bidirectional"))
      (node (ref "U$1") (pin "9") (pinfunction "9_9") (pintype "bidirectional"))
      (node (ref "U1") (pin "5") (pinfunction "VOUT_5") (pintype "passive"))
      (node (ref "U2") (pin "18") (pinfunction "AVCC_18") (pintype "power_in"))
      (node (ref "U2") (pin "4") (pinfunction "VCC_4") (pintype "power_in"))
      (node (ref "U2") (pin "6") (pinfunction "VCC_6") (pintype "power_in"))
    )
    (net (code "66") (name "unconnected-(B1-PadPOS2)") (class "Default")
      (node (ref "B1") (pin "POS2") (pinfunction "POS2_POS2") (pintype "passive"))
    )
    (net (code "67") (name "unconnected-(U3-SCL20-Pad20)") (class "Default")
      (node (ref "U3") (pin "20") (pinfunction "SCL20_20") (pintype "bidirectional"))
    )
    (net (code "68") (name "unconnected-(U3-{slash}RST-Pad6)") (class "Default")
      (node (ref "U3") (pin "6") (pinfunction "/RST_6") (pintype "bidirectional"))
    )
    (net (code "69") (name "unconnected-(U4-NC1-Pad1)") (class "Default")
      (node (ref "U4") (pin "1") (pinfunction "NC1_1") (pintype "bidirectional"))
    )
    (net (code "70") (name "unconnected-(U4-NC2-Pad2)") (class "Default")
      (node (ref "U4") (pin "2") (pinfunction "NC2_2") (pintype "bidirectional"))
    )
    (net (code "71") (name "unconnected-(U5-NC1-Pad1)") (class "Default")
      (node (ref "U5") (pin "1") (pinfunction "NC1_1") (pintype "bidirectional"))
    )
    (net (code "72") (name "unconnected-(U5-NC2-Pad2)") (class "Default")
      (node (ref "U5") (pin "2") (pinfunction "NC2_2") (pintype "bidirectional"))
    )
  )
)
